# Nusbio_smd.net
KiCad netlist of a schematic drawn in EAGLE
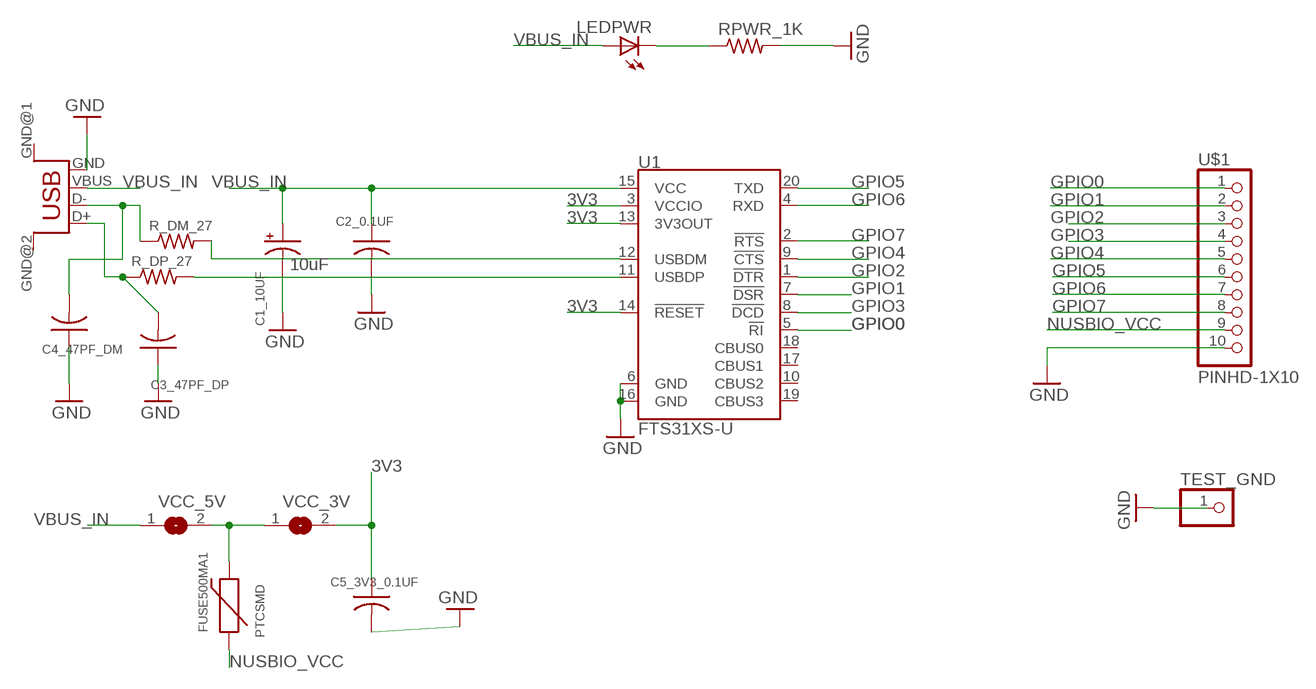
[diagram p0: schematic, sheet 1]

(export (version "E")
  (design (tool "Eeschema 10.0.6"))
  (components
    (comp (ref "C1_10UF")
      (value "10uF")
      (footprint "eagle-import:EIA3216")
      (libsource (lib "eagle-import") (part "10UF-16V-10%(TANT)"))
    )
    (comp (ref "C2_0.1UF")
      (value "C-USC1206")
      (footprint "eagle-import:C1206")
      (libsource (lib "eagle-import") (part "C-USC1206"))
    )
    (comp (ref "C3_47PF_DP")
      (value "C-USC1206")
      (footprint "eagle-import:C1206")
      (libsource (lib "eagle-import") (part "C-USC1206"))
    )
    (comp (ref "C4_47PF_DM")
      (value "C-USC1206")
      (footprint "eagle-import:C1206")
      (libsource (lib "eagle-import") (part "C-USC1206"))
    )
    (comp (ref "C5_3V3_0.1UF")
      (value "C-USC1206")
      (footprint "eagle-import:C1206")
      (libsource (lib "eagle-import") (part "C-USC1206"))
    )
    (comp (ref "FUSE500MA1")
      (value "PTCSMD")
      (footprint "eagle-import:PTC-1206")
      (libsource (lib "eagle-import") (part "PTCSMD"))
    )
    (comp (ref "LEDPWR")
      (value "LEDCHIPLED_0805")
      (footprint "eagle-import:CHIPLED_0805")
      (libsource (lib "eagle-import") (part "LEDCHIPLED_0805"))
    )
    (comp (ref "RPWR_1K")
      (value "R-US_R0805")
      (footprint "eagle-import:R0805")
      (libsource (lib "eagle-import") (part "R-US_R0805"))
    )
    (comp (ref "R_DM_27")
      (value "R-US_R0805")
      (footprint "eagle-import:R0805")
      (libsource (lib "eagle-import") (part "R-US_R0805"))
    )
    (comp (ref "R_DP_27")
      (value "R-US_R0805")
      (footprint "eagle-import:R0805")
      (libsource (lib "eagle-import") (part "R-US_R0805"))
    )
    (comp (ref "TEST_GND")
      (value "PINHD-1X1")
      (footprint "eagle-import:1X01")
      (libsource (lib "eagle-import") (part "PINHD-1X1"))
    )
    (comp (ref "U$1")
      (value "PINHD-1X10")
      (footprint "eagle-import:1X10-BIG")
      (libsource (lib "eagle-import") (part "PINHD-1X10"))
    )
    (comp (ref "U1")
      (value "FTS31XS-U")
      (footprint "eagle-import:SSOP20_L")
      (libsource (lib "eagle-import") (part "FT231XS"))
    )
    (comp (ref "USB_FEMALE")
      (value "USB")
      (footprint "eagle-import:USB-FEMALE-A-PTH")
      (libsource (lib "eagle-import") (part "USB"))
    )
    (comp (ref "VCC_3V")
      (value "SOLDERJUMPERREFLOW")
      (footprint "eagle-import:SOLDERJUMPER_REFLOW")
      (libsource (lib "eagle-import") (part "SOLDERJUMPERREFLOW"))
    )
    (comp (ref "VCC_5V")
      (value "SOLDERJUMPERREFLOW")
      (footprint "eagle-import:SOLDERJUMPER_REFLOW")
      (libsource (lib "eagle-import") (part "SOLDERJUMPERREFLOW"))
    )
  )
  (nets
    (net (code "1") (name "/3V3") (class "Default")
      (node (ref "C5_3V3_0.1UF") (pin "1") (pinfunction "1_1") (pintype "passive"))
      (node (ref "U1") (pin "13") (pinfunction "3V3OUT_13") (pintype "bidirectional"))
      (node (ref "U1") (pin "14") (pinfunction "~{RESET}_14") (pintype "bidirectional"))
      (node (ref "U1") (pin "3") (pinfunction "VCCIO_3") (pintype "bidirectional"))
      (node (ref "VCC_3V") (pin "2") (pinfunction "2_2") (pintype "passive"))
    )
    (net (code "2") (name "/GPIO0") (class "Default")
      (node (ref "U$1") (pin "1") (pinfunction "1_1") (pintype "passive"))
      (node (ref "U1") (pin "5") (pinfunction "~{RI}_5") (pintype "bidirectional"))
    )
    (net (code "3") (name "/GPIO1") (class "Default")
      (node (ref "U$1") (pin "2") (pinfunction "2_2") (pintype "passive"))
      (node (ref "U1") (pin "7") (pinfunction "~{DSR}_7") (pintype "bidirectional"))
    )
    (net (code "4") (name "/GPIO2") (class "Default")
      (node (ref "U$1") (pin "3") (pinfunction "3_3") (pintype "passive"))
      (node (ref "U1") (pin "1") (pinfunction "~{DTR}_1") (pintype "bidirectional"))
    )
    (net (code "5") (name "/GPIO3") (class "Default")
      (node (ref "U$1") (pin "4") (pinfunction "4_4") (pintype "passive"))
      (node (ref "U1") (pin "8") (pinfunction "~{DCD}_8") (pintype "bidirectional"))
    )
    (net (code "6") (name "/GPIO4") (class "Default")
      (node (ref "U$1") (pin "5") (pinfunction "5_5") (pintype "passive"))
      (node (ref "U1") (pin "9") (pinfunction "~{CTS}_9") (pintype "bidirectional"))
    )
    (net (code "7") (name "/GPIO5") (class "Default")
      (node (ref "U$1") (pin "6") (pinfunction "6_6") (pintype "passive"))
      (node (ref "U1") (pin "20") (pinfunction "TXD_20") (pintype "bidirectional"))
    )
    (net (code "8") (name "/GPIO6") (class "Default")
      (node (ref "U$1") (pin "7") (pinfunction "7_7") (pintype "passive"))
      (node (ref "U1") (pin "4") (pinfunction "RXD_4") (pintype "bidirectional"))
    )
    (net (code "9") (name "/GPIO7") (class "Default")
      (node (ref "U$1") (pin "8") (pinfunction "8_8") (pintype "passive"))
      (node (ref "U1") (pin "2") (pinfunction "~{RTS}_2") (pintype "bidirectional"))
    )
    (net (code "10") (name "/NUSBIO_VCC") (class "Default")
      (node (ref "FUSE500MA1") (pin "1") (pinfunction "1_1") (pintype "bidirectional"))
      (node (ref "U$1") (pin "9") (pinfunction "9_9") (pintype "passive"))
    )
    (net (code "11") (name "/VBUS_IN") (class "Default")
      (node (ref "C1_10UF") (pin "A") (pinfunction "+_A") (pintype "passive"))
      (node (ref "C2_0.1UF") (pin "1") (pinfunction "1_1") (pintype "passive"))
      (node (ref "LEDPWR") (pin "A") (pinfunction "A_A") (pintype "passive"))
      (node (ref "U1") (pin "15") (pinfunction "VCC_15") (pintype "bidirectional"))
      (node (ref "USB_FEMALE") (pin "VBUS") (pinfunction "VBUS_VBUS") (pintype "bidirectional"))
      (node (ref "VCC_5V") (pin "1") (pinfunction "1_1") (pintype "passive"))
    )
    (net (code "12") (name "GND") (class "Default")
      (node (ref "C1_10UF") (pin "C") (pinfunction "-_C") (pintype "passive"))
      (node (ref "C2_0.1UF") (pin "2") (pinfunction "2_2") (pintype "passive"))
      (node (ref "C3_47PF_DP") (pin "1") (pinfunction "1_1") (pintype "passive"))
      (node (ref "C4_47PF_DM") (pin "1") (pinfunction "1_1") (pintype "passive"))
      (node (ref "C5_3V3_0.1UF") (pin "2") (pinfunction "2_2") (pintype "passive"))
      (node (ref "RPWR_1K") (pin "2") (pinfunction "2_2") (pintype "passive"))
      (node (ref "TEST_GND") (pin "1") (pinfunction "1_1") (pintype "passive"))
      (node (ref "U$1") (pin "10") (pinfunction "10_10") (pintype "passive"))
      (node (ref "U1") (pin "16") (pinfunction "GND_16") (pintype "bidirectional"))
      (node (ref "U1") (pin "6") (pinfunction "GND_6") (pintype "bidirectional"))
      (node (ref "USB_FEMALE") (pin "GND") (pinfunction "GND_GND") (pintype "bidirectional"))
    )
    (net (code "13") (name "Net-(C3_47PF_DP-Pad2)") (class "Default")
      (node (ref "C3_47PF_DP") (pin "2") (pinfunction "2_2") (pintype "passive"))
      (node (ref "R_DP_27") (pin "1") (pinfunction "1_1") (pintype "passive"))
      (node (ref "USB_FEMALE") (pin "D+") (pinfunction "D+_D+") (pintype "bidirectional"))
    )
    (net (code "14") (name "Net-(C4_47PF_DM-Pad2)") (class "Default")
      (node (ref "C4_47PF_DM") (pin "2") (pinfunction "2_2") (pintype "passive"))
      (node (ref "R_DM_27") (pin "1") (pinfunction "1_1") (pintype "passive"))
      (node (ref "USB_FEMALE") (pin "D-") (pinfunction "D-_D-") (pintype "bidirectional"))
    )
    (net (code "15") (name "Net-(FUSE500MA1-Pad2)") (class "Default")
      (node (ref "FUSE500MA1") (pin "2") (pinfunction "2_2") (pintype "bidirectional"))
      (node (ref "VCC_3V") (pin "1") (pinfunction "1_1") (pintype "passive"))
      (node (ref "VCC_5V") (pin "2") (pinfunction "2_2") (pintype "passive"))
    )
    (net (code "16") (name "Net-(LEDPWR-PadC)") (class "Default")
      (node (ref "LEDPWR") (pin "C") (pinfunction "C_C") (pintype "passive"))
      (node (ref "RPWR_1K") (pin "1") (pinfunction "1_1") (pintype "passive"))
    )
    (net (code "17") (name "Net-(U1-USBDM)") (class "Default")
      (node (ref "R_DM_27") (pin "2") (pinfunction "2_2") (pintype "passive"))
      (node (ref "U1") (pin "12") (pinfunction "USBDM_12") (pintype "bidirectional"))
    )
    (net (code "18") (name "Net-(U1-USBDP)") (class "Default")
      (node (ref "R_DP_27") (pin "2") (pinfunction "2_2") (pintype "passive"))
      (node (ref "U1") (pin "11") (pinfunction "USBDP_11") (pintype "bidirectional"))
    )
    (net (code "19") (name "unconnected-(U1-CBUS0-Pad18)") (class "Default")
      (node (ref "U1") (pin "18") (pinfunction "CBUS0_18") (pintype "bidirectional"))
    )
    (net (code "20") (name "unconnected-(U1-CBUS1-Pad17)") (class "Default")
      (node (ref "U1") (pin "17") (pinfunction "CBUS1_17") (pintype "bidirectional"))
    )
    (net (code "21") (name "unconnected-(U1-CBUS2-Pad10)") (class "Default")
      (node (ref "U1") (pin "10") (pinfunction "CBUS2_10") (pintype "bidirectional"))
    )
    (net (code "22") (name "unconnected-(U1-CBUS3-Pad19)") (class "Default")
      (node (ref "U1") (pin "19") (pinfunction "CBUS3_19") (pintype "bidirectional"))
    )
    (net (code "23") (name "unconnected-(USB_FEMALE-GND-PadGND@1)") (class "Default")
      (node (ref "USB_FEMALE") (pin "GND@1") (pinfunction "GND_GND@1") (pintype "bidirectional"))
    )
    (net (code "24") (name "unconnected-(USB_FEMALE-GND-PadGND@2)") (class "Default")
      (node (ref "USB_FEMALE") (pin "GND@2") (pinfunction "GND_GND@2") (pintype "bidirectional"))
    )
  )
)
